# M_D_ext_power.net
KiCad netlist of a schematic drawn in EAGLE
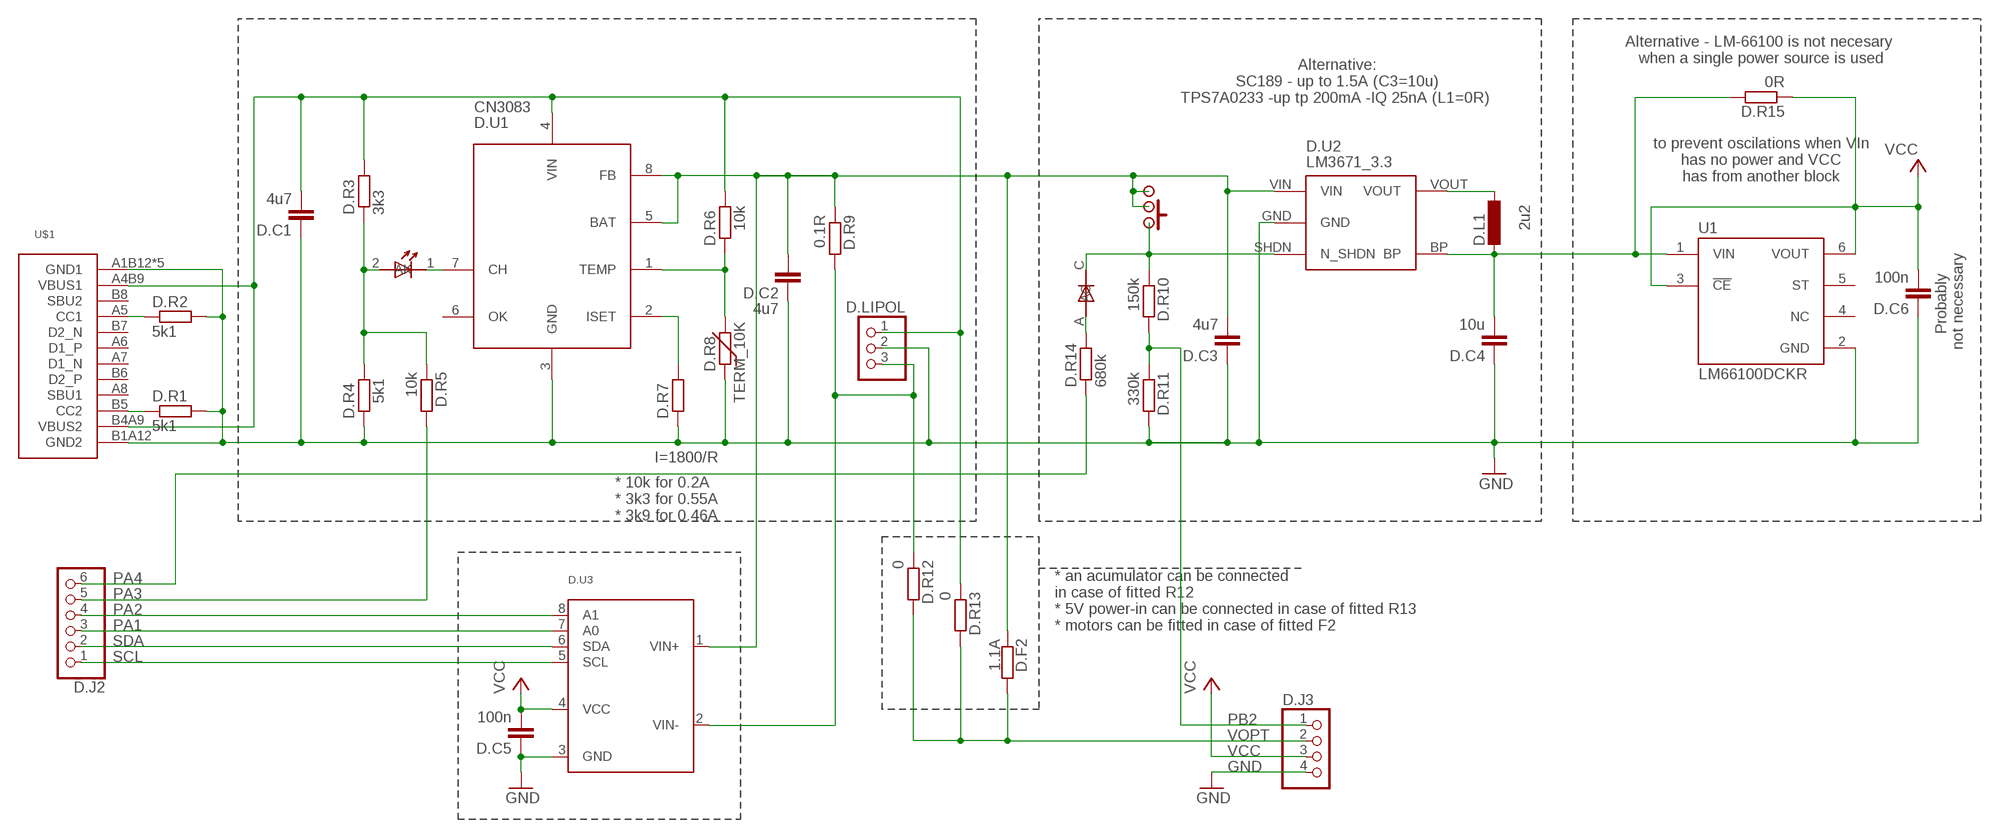
[diagram p0: schematic, sheet 1]

(export (version "E")
  (design (tool "Eeschema 10.0.6"))
  (components
    (comp (ref "D.C1")
      (value "4u7")
      (footprint "eagle-import:C0603")
      (libsource (lib "eagle-import") (part "C-EUC0603"))
    )
    (comp (ref "D.C2")
      (value "4u7")
      (footprint "eagle-import:C0603")
      (libsource (lib "eagle-import") (part "C-EUC0603"))
    )
    (comp (ref "D.C3")
      (value "4u7")
      (footprint "eagle-import:C0603")
      (libsource (lib "eagle-import") (part "C-EUC0603"))
    )
    (comp (ref "D.C4")
      (value "10u")
      (footprint "eagle-import:C0603")
      (libsource (lib "eagle-import") (part "C-EUC0603"))
    )
    (comp (ref "D.C5")
      (value "100n")
      (footprint "eagle-import:C0603")
      (libsource (lib "eagle-import") (part "C-EUC0603"))
    )
    (comp (ref "D.C6")
      (value "100n")
      (footprint "eagle-import:C0603")
      (libsource (lib "eagle-import") (part "C-EUC0603"))
    )
    (comp (ref "D.D1")
      (value "LED_1.8")
      (footprint "eagle-import:LED_1.8")
      (libsource (lib "eagle-import") (part "LED_1.8"))
    )
    (comp (ref "D.D2")
      (value "DIODE")
      (footprint "eagle-import:DIODE")
      (libsource (lib "eagle-import") (part "DIODE"))
    )
    (comp (ref "D.F2")
      (value "1.1A")
      (footprint "eagle-import:R0805")
      (libsource (lib "eagle-import") (part "R-EU_R0805"))
    )
    (comp (ref "D.J2")
      (value "PINHD-1X6")
      (footprint "eagle-import:1X06")
      (libsource (lib "eagle-import") (part "PINHD-1X6"))
    )
    (comp (ref "D.J3")
      (value "PINHD-1X4")
      (footprint "eagle-import:1X04")
      (libsource (lib "eagle-import") (part "PINHD-1X4"))
    )
    (comp (ref "D.L1")
      (value "2u2")
      (footprint "eagle-import:L3230M")
      (libsource (lib "eagle-import") (part "L-EUL3230M"))
    )
    (comp (ref "D.LIPOL")
      (value "PINHEAD-1X3-2")
      (footprint "eagle-import:1X-03-2")
      (libsource (lib "eagle-import") (part "PINHEAD-1X3-2"))
    )
    (comp (ref "D.ON/OFF/RESET")
      (value "SWITCH")
      (footprint "eagle-import:SWITCH")
      (libsource (lib "eagle-import") (part "SWITCH"))
    )
    (comp (ref "D.R1")
      (value "5k1")
      (footprint "eagle-import:R0603")
      (libsource (lib "eagle-import") (part "R-EU_R0603"))
    )
    (comp (ref "D.R2")
      (value "5k1")
      (footprint "eagle-import:R0603")
      (libsource (lib "eagle-import") (part "R-EU_R0603"))
    )
    (comp (ref "D.R3")
      (value "3k3")
      (footprint "eagle-import:R0603")
      (libsource (lib "eagle-import") (part "R-EU_R0603"))
    )
    (comp (ref "D.R4")
      (value "5k1")
      (footprint "eagle-import:R0603")
      (libsource (lib "eagle-import") (part "R-EU_R0603"))
    )
    (comp (ref "D.R5")
      (value "10k")
      (footprint "eagle-import:R0603")
      (libsource (lib "eagle-import") (part "R-EU_R0603"))
    )
    (comp (ref "D.R6")
      (value "10k")
      (footprint "eagle-import:R0603")
      (libsource (lib "eagle-import") (part "R-EU_R0603"))
    )
    (comp (ref "D.R7")
      (value "I=1800/R")
      (footprint "eagle-import:R0603")
      (libsource (lib "eagle-import") (part "R-EU_R0603"))
    )
    (comp (ref "D.R8")
      (value "TERM_10K")
      (footprint "eagle-import:THERM")
      (libsource (lib "eagle-import") (part "THERM"))
    )
    (comp (ref "D.R9")
      (value "0.1R")
      (footprint "eagle-import:R0805")
      (libsource (lib "eagle-import") (part "R-EU_R0805"))
    )
    (comp (ref "D.R10")
      (value "150k")
      (footprint "eagle-import:R0603")
      (libsource (lib "eagle-import") (part "R-EU_R0603"))
    )
    (comp (ref "D.R11")
      (value "330k")
      (footprint "eagle-import:R0603")
      (libsource (lib "eagle-import") (part "R-EU_R0603"))
    )
    (comp (ref "D.R12")
      (value "0")
      (footprint "eagle-import:R0603")
      (libsource (lib "eagle-import") (part "R-EU_R0603"))
    )
    (comp (ref "D.R13")
      (value "0")
      (footprint "eagle-import:R0603")
      (libsource (lib "eagle-import") (part "R-EU_R0603"))
    )
    (comp (ref "D.R14")
      (value "680k")
      (footprint "eagle-import:R0603")
      (libsource (lib "eagle-import") (part "R-EU_R0603"))
    )
    (comp (ref "D.R15")
      (value "0R")
      (footprint "eagle-import:R0603")
      (libsource (lib "eagle-import") (part "R-EU_R0603"))
    )
    (comp (ref "D.U1")
      (value "CN3083")
      (footprint "eagle-import:SOP8")
      (libsource (lib "eagle-import") (part "CN3083"))
    )
    (comp (ref "D.U2")
      (value "LM3671_3.3")
      (footprint "eagle-import:SOT32-5")
      (libsource (lib "eagle-import") (part "STABILISER_APE8865"))
    )
    (comp (ref "D.U3")
      (value "INA219")
      (footprint "eagle-import:SOT23-8")
      (libsource (lib "eagle-import") (part "INA219"))
    )
    (comp (ref "U$1")
      (value "USB-C")
      (footprint "eagle-import:USB-C")
      (libsource (lib "eagle-import") (part "USB-C"))
    )
    (comp (ref "U1")
      (value "LM66100DCKR")
      (footprint "eagle-import:SOT65P210X110-6N")
      (fields (field (name "MF") "Texas Instruments"))
      (libsource (lib "eagle-import") (part "LM66100DCKR"))
    )
  )
  (nets
    (net (code "1") (name "/PA1") (class "Default")
      (node (ref "D.J2") (pin "3") (pinfunction "3_3") (pintype "passive"))
      (node (ref "D.U3") (pin "7") (pinfunction "A0_7") (pintype "bidirectional"))
    )
    (net (code "2") (name "/PA2") (class "Default")
      (node (ref "D.J2") (pin "4") (pinfunction "4_4") (pintype "passive"))
      (node (ref "D.U3") (pin "8") (pinfunction "A1_8") (pintype "bidirectional"))
    )
    (net (code "3") (name "/PA3") (class "Default")
      (node (ref "D.J2") (pin "5") (pinfunction "5_5") (pintype "passive"))
      (node (ref "D.R5") (pin "2") (pinfunction "2_2") (pintype "passive"))
    )
    (net (code "4") (name "/PA4") (class "Default")
      (node (ref "D.J2") (pin "6") (pinfunction "6_6") (pintype "passive"))
      (node (ref "D.R14") (pin "1") (pinfunction "1_1") (pintype "passive"))
    )
    (net (code "5") (name "/PB2") (class "Default")
      (node (ref "D.J3") (pin "1") (pinfunction "1_1") (pintype "passive"))
      (node (ref "D.R10") (pin "2") (pinfunction "2_2") (pintype "passive"))
      (node (ref "D.R11") (pin "1") (pinfunction "1_1") (pintype "passive"))
    )
    (net (code "6") (name "/SCL") (class "Default")
      (node (ref "D.J2") (pin "1") (pinfunction "1_1") (pintype "passive"))
      (node (ref "D.U3") (pin "5") (pinfunction "SCL_5") (pintype "bidirectional"))
    )
    (net (code "7") (name "/SDA") (class "Default")
      (node (ref "D.J2") (pin "2") (pinfunction "2_2") (pintype "passive"))
      (node (ref "D.U3") (pin "6") (pinfunction "SDA_6") (pintype "bidirectional"))
    )
    (net (code "8") (name "/VOPT") (class "Default")
      (node (ref "D.F2") (pin "2") (pinfunction "2_2") (pintype "passive"))
      (node (ref "D.J3") (pin "2") (pinfunction "2_2") (pintype "passive"))
      (node (ref "D.R12") (pin "2") (pinfunction "2_2") (pintype "passive"))
      (node (ref "D.R13") (pin "2") (pinfunction "2_2") (pintype "passive"))
    )
    (net (code "9") (name "GND") (class "Default")
      (node (ref "D.C1") (pin "1") (pinfunction "1_1") (pintype "passive"))
      (node (ref "D.C2") (pin "1") (pinfunction "1_1") (pintype "passive"))
      (node (ref "D.C3") (pin "1") (pinfunction "1_1") (pintype "passive"))
      (node (ref "D.C4") (pin "1") (pinfunction "1_1") (pintype "passive"))
      (node (ref "D.C5") (pin "1") (pinfunction "1_1") (pintype "passive"))
      (node (ref "D.C6") (pin "1") (pinfunction "1_1") (pintype "passive"))
      (node (ref "D.J3") (pin "4") (pinfunction "4_4") (pintype "passive"))
      (node (ref "D.LIPOL") (pin "2") (pinfunction "2_2") (pintype "passive"))
      (node (ref "D.R1") (pin "2") (pinfunction "2_2") (pintype "passive"))
      (node (ref "D.R11") (pin "2") (pinfunction "2_2") (pintype "passive"))
      (node (ref "D.R2") (pin "2") (pinfunction "2_2") (pintype "passive"))
      (node (ref "D.R4") (pin "1") (pinfunction "1_1") (pintype "passive"))
      (node (ref "D.R7") (pin "1") (pinfunction "1_1") (pintype "passive"))
      (node (ref "D.R8") (pin "1") (pinfunction "1_1") (pintype "passive"))
      (node (ref "D.U1") (pin "3") (pinfunction "GND_3") (pintype "bidirectional"))
      (node (ref "D.U2") (pin "GND") (pinfunction "GND_GND") (pintype "bidirectional"))
      (node (ref "D.U3") (pin "3") (pinfunction "GND_3") (pintype "bidirectional"))
      (node (ref "U$1") (pin "A1B12") (pinfunction "GND1_A1B12") (pintype "bidirectional"))
      (node (ref "U$1") (pin "B1A12") (pinfunction "GND2_B1A12") (pintype "bidirectional"))
      (node (ref "U$1") (pin "SH1") (pinfunction "GND1_SH1") (pintype "bidirectional"))
      (node (ref "U$1") (pin "SH2") (pinfunction "GND1_SH2") (pintype "bidirectional"))
      (node (ref "U$1") (pin "SH3") (pinfunction "GND1_SH3") (pintype "bidirectional"))
      (node (ref "U$1") (pin "SH4") (pinfunction "GND1_SH4") (pintype "bidirectional"))
      (node (ref "U1") (pin "2") (pinfunction "GND_2") (pintype "power_in"))
    )
    (net (code "10") (name "Net-(D.D1-A)") (class "Default")
      (node (ref "D.D1") (pin "2") (pinfunction "A_2") (pintype "bidirectional"))
      (node (ref "D.R3") (pin "1") (pinfunction "1_1") (pintype "passive"))
      (node (ref "D.R4") (pin "2") (pinfunction "2_2") (pintype "passive"))
      (node (ref "D.R5") (pin "1") (pinfunction "1_1") (pintype "passive"))
    )
    (net (code "11") (name "Net-(D.D1-K)") (class "Default")
      (node (ref "D.D1") (pin "1") (pinfunction "K_1") (pintype "bidirectional"))
      (node (ref "D.U1") (pin "7") (pinfunction "CH_7") (pintype "bidirectional"))
    )
    (net (code "12") (name "Net-(D.D2-PadA)") (class "Default")
      (node (ref "D.D2") (pin "A") (pinfunction "A_A") (pintype "bidirectional"))
      (node (ref "D.R14") (pin "2") (pinfunction "2_2") (pintype "passive"))
    )
    (net (code "13") (name "Net-(D.L1-Pad1)") (class "Default")
      (node (ref "D.L1") (pin "1") (pinfunction "1_1") (pintype "passive"))
      (node (ref "D.U2") (pin "VOUT") (pinfunction "VOUT_VOUT") (pintype "bidirectional"))
    )
    (net (code "14") (name "Net-(D.U1-BAT)") (class "Default")
      (node (ref "D.C2") (pin "2") (pinfunction "2_2") (pintype "passive"))
      (node (ref "D.C3") (pin "2") (pinfunction "2_2") (pintype "passive"))
      (node (ref "D.F2") (pin "1") (pinfunction "1_1") (pintype "passive"))
      (node (ref "D.ON/OFF/RESET") (pin "P$2") (pinfunction "P$2_P$2") (pintype "bidirectional"))
      (node (ref "D.ON/OFF/RESET") (pin "P$3") (pinfunction "P$3_P$3") (pintype "bidirectional"))
      (node (ref "D.ON/OFF/RESET") (pin "P$4") (pinfunction "P$3_P$4") (pintype "bidirectional"))
      (node (ref "D.ON/OFF/RESET") (pin "P$6") (pinfunction "P$3_P$6") (pintype "bidirectional"))
      (node (ref "D.R9") (pin "1") (pinfunction "1_1") (pintype "passive"))
      (node (ref "D.U1") (pin "5") (pinfunction "BAT_5") (pintype "bidirectional"))
      (node (ref "D.U1") (pin "8") (pinfunction "FB_8") (pintype "bidirectional"))
      (node (ref "D.U2") (pin "VIN") (pinfunction "VIN_VIN") (pintype "bidirectional"))
      (node (ref "D.U3") (pin "1") (pinfunction "VIN+_1") (pintype "bidirectional"))
    )
    (net (code "15") (name "Net-(D.U1-ISET)") (class "Default")
      (node (ref "D.R7") (pin "2") (pinfunction "2_2") (pintype "passive"))
      (node (ref "D.U1") (pin "2") (pinfunction "ISET_2") (pintype "bidirectional"))
    )
    (net (code "16") (name "Net-(D.U1-TEMP)") (class "Default")
      (node (ref "D.R6") (pin "1") (pinfunction "1_1") (pintype "passive"))
      (node (ref "D.R8") (pin "2") (pinfunction "2_2") (pintype "passive"))
      (node (ref "D.U1") (pin "1") (pinfunction "TEMP_1") (pintype "bidirectional"))
    )
    (net (code "17") (name "Net-(D.U1-VIN)") (class "Default")
      (node (ref "D.C1") (pin "2") (pinfunction "2_2") (pintype "passive"))
      (node (ref "D.LIPOL") (pin "1") (pinfunction "1_1") (pintype "passive"))
      (node (ref "D.R13") (pin "1") (pinfunction "1_1") (pintype "passive"))
      (node (ref "D.R3") (pin "2") (pinfunction "2_2") (pintype "passive"))
      (node (ref "D.R6") (pin "2") (pinfunction "2_2") (pintype "passive"))
      (node (ref "D.U1") (pin "4") (pinfunction "VIN_4") (pintype "bidirectional"))
      (node (ref "U$1") (pin "A4B9") (pinfunction "VBUS1_A4B9") (pintype "bidirectional"))
      (node (ref "U$1") (pin "B4A9") (pinfunction "VBUS2_B4A9") (pintype "bidirectional"))
    )
    (net (code "18") (name "Net-(D.U2-N_SHDN)") (class "Default")
      (node (ref "D.D2") (pin "C") (pinfunction "C_C") (pintype "bidirectional"))
      (node (ref "D.ON/OFF/RESET") (pin "P$1") (pinfunction "P$1_P$1") (pintype "bidirectional"))
      (node (ref "D.ON/OFF/RESET") (pin "P$5") (pinfunction "P$1_P$5") (pintype "bidirectional"))
      (node (ref "D.ON/OFF/RESET") (pin "P$7") (pinfunction "P$1_P$7") (pintype "bidirectional"))
      (node (ref "D.R10") (pin "1") (pinfunction "1_1") (pintype "passive"))
      (node (ref "D.U2") (pin "SHDN") (pinfunction "N_SHDN_SHDN") (pintype "bidirectional"))
    )
    (net (code "19") (name "Net-(D.U3-VIN-)") (class "Default")
      (node (ref "D.LIPOL") (pin "3") (pinfunction "3_3") (pintype "passive"))
      (node (ref "D.R12") (pin "1") (pinfunction "1_1") (pintype "passive"))
      (node (ref "D.R9") (pin "2") (pinfunction "2_2") (pintype "passive"))
      (node (ref "D.U3") (pin "2") (pinfunction "VIN-_2") (pintype "bidirectional"))
    )
    (net (code "20") (name "Net-(U$1-CC1)") (class "Default")
      (node (ref "D.R2") (pin "1") (pinfunction "1_1") (pintype "passive"))
      (node (ref "U$1") (pin "A5") (pinfunction "CC1_A5") (pintype "bidirectional"))
    )
    (net (code "21") (name "Net-(U$1-CC2)") (class "Default")
      (node (ref "D.R1") (pin "1") (pinfunction "1_1") (pintype "passive"))
      (node (ref "U$1") (pin "B5") (pinfunction "CC2_B5") (pintype "bidirectional"))
    )
    (net (code "22") (name "Net-(U1-VIN)") (class "Default")
      (node (ref "D.C4") (pin "2") (pinfunction "2_2") (pintype "passive"))
      (node (ref "D.L1") (pin "2") (pinfunction "2_2") (pintype "passive"))
      (node (ref "D.R15") (pin "2") (pinfunction "2_2") (pintype "passive"))
      (node (ref "D.U2") (pin "BP") (pinfunction "BP_BP") (pintype "bidirectional"))
      (node (ref "U1") (pin "1") (pinfunction "VIN_1") (pintype "input"))
    )
    (net (code "23") (name "VCC") (class "Default")
      (node (ref "D.C5") (pin "2") (pinfunction "2_2") (pintype "passive"))
      (node (ref "D.C6") (pin "2") (pinfunction "2_2") (pintype "passive"))
      (node (ref "D.J3") (pin "3") (pinfunction "3_3") (pintype "passive"))
      (node (ref "D.R15") (pin "1") (pinfunction "1_1") (pintype "passive"))
      (node (ref "D.U3") (pin "4") (pinfunction "VCC_4") (pintype "bidirectional"))
      (node (ref "U1") (pin "3") (pinfunction "~{CE}_3") (pintype "input"))
      (node (ref "U1") (pin "6") (pinfunction "VOUT_6") (pintype "output"))
    )
    (net (code "24") (name "unconnected-(D.U1-OK-Pad6)") (class "Default")
      (node (ref "D.U1") (pin "6") (pinfunction "OK_6") (pintype "bidirectional"))
    )
    (net (code "25") (name "unconnected-(U$1-D1_N-PadA7)") (class "Default")
      (node (ref "U$1") (pin "A7") (pinfunction "D1_N_A7") (pintype "bidirectional"))
    )
    (net (code "26") (name "unconnected-(U$1-D1_P-PadA6)") (class "Default")
      (node (ref "U$1") (pin "A6") (pinfunction "D1_P_A6") (pintype "bidirectional"))
    )
    (net (code "27") (name "unconnected-(U$1-D2_N-PadB7)") (class "Default")
      (node (ref "U$1") (pin "B7") (pinfunction "D2_N_B7") (pintype "bidirectional"))
    )
    (net (code "28") (name "unconnected-(U$1-D2_P-PadB6)") (class "Default")
      (node (ref "U$1") (pin "B6") (pinfunction "D2_P_B6") (pintype "bidirectional"))
    )
    (net (code "29") (name "unconnected-(U$1-SBU1-PadA8)") (class "Default")
      (node (ref "U$1") (pin "A8") (pinfunction "SBU1_A8") (pintype "bidirectional"))
    )
    (net (code "30") (name "unconnected-(U$1-SBU2-PadB8)") (class "Default")
      (node (ref "U$1") (pin "B8") (pinfunction "SBU2_B8") (pintype "bidirectional"))
    )
    (net (code "31") (name "unconnected-(U1-NC-Pad4)") (class "Default")
      (node (ref "U1") (pin "4") (pinfunction "NC_4") (pintype "no_connect"))
    )
    (net (code "32") (name "unconnected-(U1-ST-Pad5)") (class "Default")
      (node (ref "U1") (pin "5") (pinfunction "ST_5") (pintype "output"))
    )
  )
)
